# design.net
KiCad netlist of a schematic drawn in EAGLE
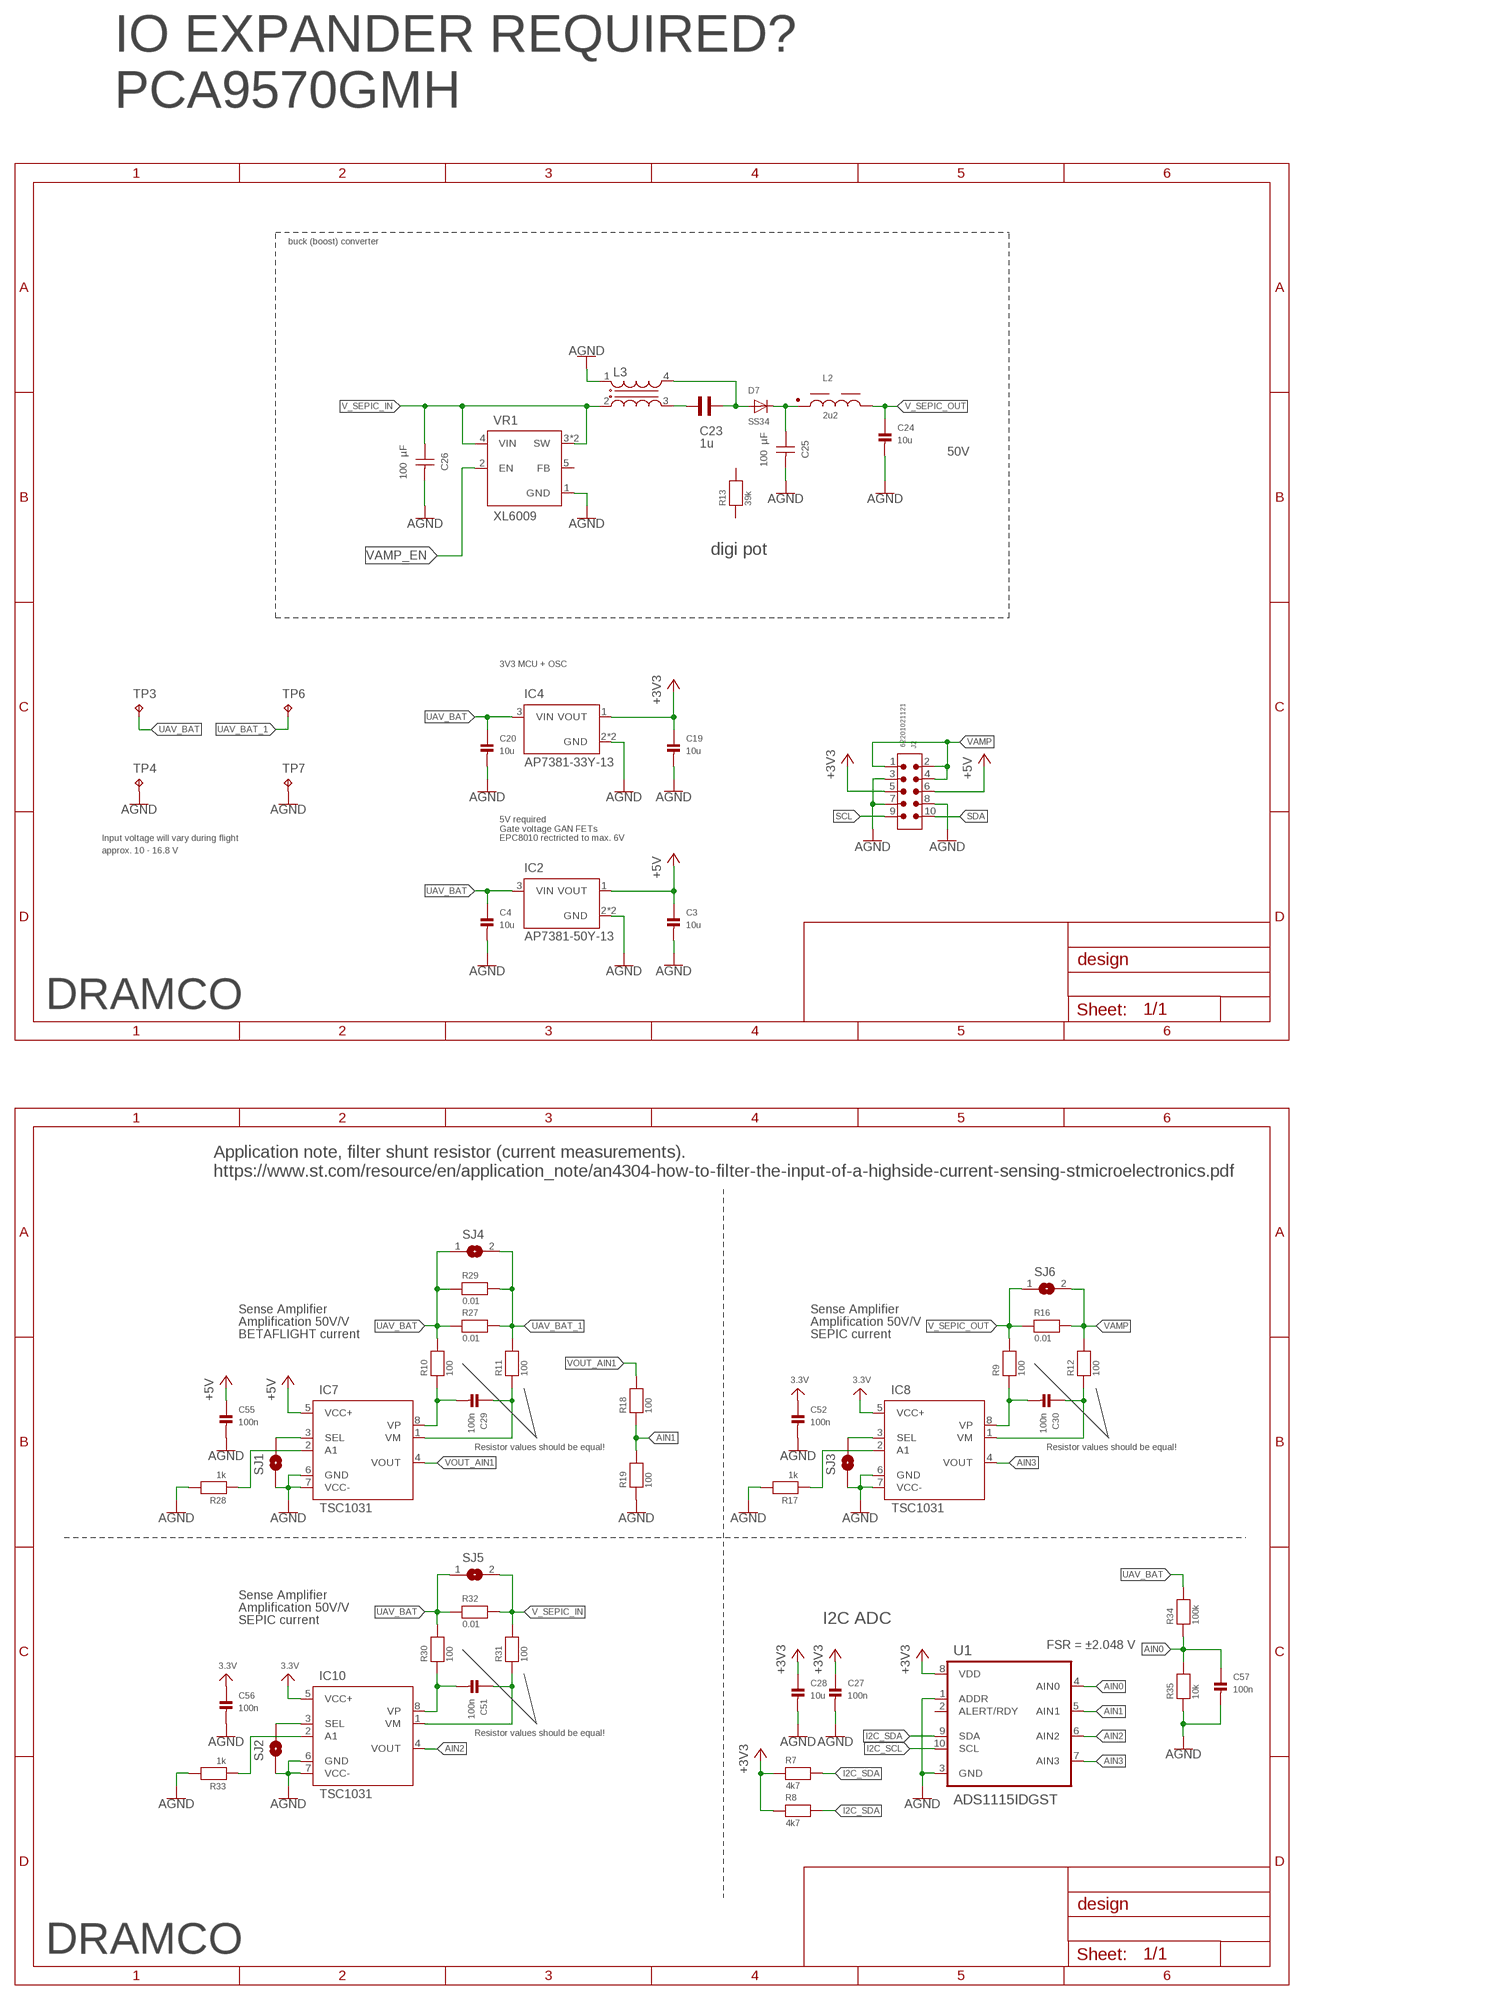
[diagram p0: schematic, sheet 1]

(export (version "E")
  (design (tool "Eeschema 10.0.6"))
  (components
    (comp (ref "C3")
      (value "10u")
      (footprint "eagle-import:0603")
      (libsource (lib "eagle-import") (part "CAP_CERAMIC0603"))
    )
    (comp (ref "C4")
      (value "10u")
      (footprint "eagle-import:0603")
      (libsource (lib "eagle-import") (part "CAP_CERAMIC0603"))
    )
    (comp (ref "C19")
      (value "10u")
      (footprint "eagle-import:0603")
      (libsource (lib "eagle-import") (part "CAP_CERAMIC0603"))
    )
    (comp (ref "C20")
      (value "10u")
      (footprint "eagle-import:0603")
      (libsource (lib "eagle-import") (part "CAP_CERAMIC0603"))
    )
    (comp (ref "C23")
      (value "1u")
      (footprint "eagle-import:WCAP-CSGP_0805_WAVE")
      (libsource (lib "eagle-import") (part "WCAP-CSGP_0805_WAVE_885012207103"))
    )
    (comp (ref "C24")
      (value "10u")
      (footprint "eagle-import:0805")
      (libsource (lib "eagle-import") (part "CAP_CERAMIC0805"))
    )
    (comp (ref "C25")
      (value "100 µF")
      (footprint "eagle-import:WCAP-ASNP_8X10.5(DXL)")
      (libsource (lib "eagle-import") (part "WCAP-ASNP_8X10.5_865250453009"))
    )
    (comp (ref "C26")
      (value "100 µF")
      (footprint "eagle-import:WCAP-ASNP_8X10.5(DXL)")
      (libsource (lib "eagle-import") (part "WCAP-ASNP_8X10.5_865250453009"))
    )
    (comp (ref "C27")
      (value "100n")
      (footprint "eagle-import:0603")
      (libsource (lib "eagle-import") (part "CAP_CERAMIC0603"))
    )
    (comp (ref "C28")
      (value "10u")
      (footprint "eagle-import:0603")
      (libsource (lib "eagle-import") (part "CAP_CERAMIC0603"))
    )
    (comp (ref "C29")
      (value "100n")
      (footprint "eagle-import:0402")
      (libsource (lib "eagle-import") (part "CAP_CERAMIC0402"))
    )
    (comp (ref "C30")
      (value "100n")
      (footprint "eagle-import:0402")
      (libsource (lib "eagle-import") (part "CAP_CERAMIC0402"))
    )
    (comp (ref "C51")
      (value "100n")
      (footprint "eagle-import:0402")
      (libsource (lib "eagle-import") (part "CAP_CERAMIC0402"))
    )
    (comp (ref "C52")
      (value "100n")
      (footprint "eagle-import:0402")
      (libsource (lib "eagle-import") (part "CAP_CERAMIC0402"))
    )
    (comp (ref "C55")
      (value "100n")
      (footprint "eagle-import:0402")
      (libsource (lib "eagle-import") (part "CAP_CERAMIC0402"))
    )
    (comp (ref "C56")
      (value "100n")
      (footprint "eagle-import:0402")
      (libsource (lib "eagle-import") (part "CAP_CERAMIC0402"))
    )
    (comp (ref "C57")
      (value "100n")
      (footprint "eagle-import:0603")
      (libsource (lib "eagle-import") (part "CAP_CERAMIC0603"))
    )
    (comp (ref "D7")
      (value "SS34")
      (footprint "eagle-import:SOD-123")
      (libsource (lib "eagle-import") (part "DIODESOD-123"))
    )
    (comp (ref "IC2")
      (value "AP7381-50Y-13")
      (footprint "eagle-import:FOOT_XC6201P332PR-G")
      (fields (field (name "MF") "Microchip") (field (name "MP") "MCP1700T-3602E/MB"))
      (libsource (lib "eagle-import") (part "AP7381-50Y-13"))
    )
    (comp (ref "IC4")
      (value "AP7381-33Y-13")
      (footprint "eagle-import:FOOT_XC6201P332PR-G")
      (fields (field (name "MF") "Microchip") (field (name "MP") "MCP1700T-3602E/MB"))
      (libsource (lib "eagle-import") (part "AP7381-50Y-13"))
    )
    (comp (ref "IC7")
      (value "TSC1031")
      (footprint "eagle-import:SOP65P640X120-8N")
      (libsource (lib "eagle-import") (part "TSC1031IPT"))
    )
    (comp (ref "IC8")
      (value "TSC1031")
      (footprint "eagle-import:SOP65P640X120-8N")
      (libsource (lib "eagle-import") (part "TSC1031IPT"))
    )
    (comp (ref "IC10")
      (value "TSC1031")
      (footprint "eagle-import:SOP65P640X120-8N")
      (libsource (lib "eagle-import") (part "TSC1031IPT"))
    )
    (comp (ref "J2")
      (value "62201021121")
      (footprint "eagle-import:62201021121")
      (libsource (lib "eagle-import") (part "6220XX21121_62201021121"))
    )
    (comp (ref "L2")
      (value "2u2")
      (footprint "eagle-import:WE-LQS_3015")
      (libsource (lib "eagle-import") (part "WE-LQS_3015_74404032022"))
    )
    (comp (ref "L3")
      (value "WE-DD_1280_744873150")
      (footprint "eagle-import:WE-DD_1260_1280")
      (libsource (lib "eagle-import") (part "WE-DD_1280_744873150"))
    )
    (comp (ref "R7")
      (value "4k7")
      (footprint "eagle-import:0603")
      (libsource (lib "eagle-import") (part "RESISTOR0603"))
    )
    (comp (ref "R8")
      (value "4k7")
      (footprint "eagle-import:0603")
      (libsource (lib "eagle-import") (part "RESISTOR0603"))
    )
    (comp (ref "R9")
      (value "100")
      (footprint "eagle-import:0603")
      (libsource (lib "eagle-import") (part "RESISTOR0603"))
    )
    (comp (ref "R10")
      (value "100")
      (footprint "eagle-import:0603")
      (libsource (lib "eagle-import") (part "RESISTOR0603"))
    )
    (comp (ref "R11")
      (value "100")
      (footprint "eagle-import:0603")
      (libsource (lib "eagle-import") (part "RESISTOR0603"))
    )
    (comp (ref "R12")
      (value "100")
      (footprint "eagle-import:0603")
      (libsource (lib "eagle-import") (part "RESISTOR0603"))
    )
    (comp (ref "R13")
      (value "39k")
      (footprint "eagle-import:0603")
      (libsource (lib "eagle-import") (part "RESISTOR0603"))
    )
    (comp (ref "R16")
      (value "0.01")
      (footprint "eagle-import:0805")
      (libsource (lib "eagle-import") (part "RESISTOR0805"))
    )
    (comp (ref "R17")
      (value "1k")
      (footprint "eagle-import:0603")
      (libsource (lib "eagle-import") (part "RESISTOR0603"))
    )
    (comp (ref "R18")
      (value "100")
      (footprint "eagle-import:0603")
      (libsource (lib "eagle-import") (part "RESISTOR0603"))
    )
    (comp (ref "R19")
      (value "100")
      (footprint "eagle-import:0603")
      (libsource (lib "eagle-import") (part "RESISTOR0603"))
    )
    (comp (ref "R27")
      (value "0.01")
      (footprint "eagle-import:0805")
      (libsource (lib "eagle-import") (part "RESISTOR0805"))
    )
    (comp (ref "R28")
      (value "1k")
      (footprint "eagle-import:0603")
      (libsource (lib "eagle-import") (part "RESISTOR0603"))
    )
    (comp (ref "R29")
      (value "0.01")
      (footprint "eagle-import:0805")
      (libsource (lib "eagle-import") (part "RESISTOR0805"))
    )
    (comp (ref "R30")
      (value "100")
      (footprint "eagle-import:0603")
      (libsource (lib "eagle-import") (part "RESISTOR0603"))
    )
    (comp (ref "R31")
      (value "100")
      (footprint "eagle-import:0603")
      (libsource (lib "eagle-import") (part "RESISTOR0603"))
    )
    (comp (ref "R32")
      (value "0.01")
      (footprint "eagle-import:0805")
      (libsource (lib "eagle-import") (part "RESISTOR0805"))
    )
    (comp (ref "R33")
      (value "1k")
      (footprint "eagle-import:0603")
      (libsource (lib "eagle-import") (part "RESISTOR0603"))
    )
    (comp (ref "R34")
      (value "100k")
      (footprint "eagle-import:0603")
      (libsource (lib "eagle-import") (part "RESISTOR0603"))
    )
    (comp (ref "R35")
      (value "10k")
      (footprint "eagle-import:0603")
      (libsource (lib "eagle-import") (part "RESISTOR0603"))
    )
    (comp (ref "SJ1")
      (value "SOLDERJUMPERTRACE")
      (footprint "eagle-import:SJ_2S-TRACE")
      (libsource (lib "eagle-import") (part "SOLDERJUMPERTRACE"))
    )
    (comp (ref "SJ2")
      (value "SOLDERJUMPERTRACE")
      (footprint "eagle-import:SJ_2S-TRACE")
      (libsource (lib "eagle-import") (part "SOLDERJUMPERTRACE"))
    )
    (comp (ref "SJ3")
      (value "SOLDERJUMPERTRACE")
      (footprint "eagle-import:SJ_2S-TRACE")
      (libsource (lib "eagle-import") (part "SOLDERJUMPERTRACE"))
    )
    (comp (ref "SJ4")
      (value "SOLDERJUMPERREFLOW")
      (footprint "eagle-import:SOLDERJUMPER_REFLOW")
      (libsource (lib "eagle-import") (part "SOLDERJUMPERREFLOW"))
    )
    (comp (ref "SJ5")
      (value "SOLDERJUMPERREFLOW")
      (footprint "eagle-import:SOLDERJUMPER_REFLOW")
      (libsource (lib "eagle-import") (part "SOLDERJUMPERREFLOW"))
    )
    (comp (ref "SJ6")
      (value "SOLDERJUMPERREFLOW")
      (footprint "eagle-import:SOLDERJUMPER_REFLOW")
      (libsource (lib "eagle-import") (part "SOLDERJUMPERREFLOW"))
    )
    (comp (ref "TP3")
      (value "TPTP20SQ")
      (footprint "eagle-import:TP20SQ")
      (libsource (lib "eagle-import") (part "TPTP20SQ"))
    )
    (comp (ref "TP4")
      (value "TPTP20SQ")
      (footprint "eagle-import:TP20SQ")
      (libsource (lib "eagle-import") (part "TPTP20SQ"))
    )
    (comp (ref "TP6")
      (value "TPTP20SQ")
      (footprint "eagle-import:TP20SQ")
      (libsource (lib "eagle-import") (part "TPTP20SQ"))
    )
    (comp (ref "TP7")
      (value "TPTP20SQ")
      (footprint "eagle-import:TP20SQ")
      (libsource (lib "eagle-import") (part "TPTP20SQ"))
    )
    (comp (ref "U1")
      (value "ADS1115IDGST")
      (footprint "eagle-import:SOP50P490X110-10N")
      (fields (field (name "MF") "Texas Instruments"))
      (libsource (lib "eagle-import") (part "ADS1115IDGST"))
    )
    (comp (ref "VR1")
      (value "XL6009")
      (footprint "eagle-import:DPAK170P1435X465-6N")
      (fields (field (name "MF") "XLSEMI"))
      (libsource (lib "eagle-import") (part "XL6009"))
    )
  )
  (nets
    (net (code "1") (name "+3V3") (class "Default")
      (node (ref "C19") (pin "1") (pinfunction "P$1_1") (pintype "passive"))
      (node (ref "C27") (pin "1") (pinfunction "P$1_1") (pintype "passive"))
      (node (ref "C28") (pin "1") (pinfunction "P$1_1") (pintype "passive"))
      (node (ref "IC4") (pin "1") (pinfunction "VOUT_1") (pintype "output"))
      (node (ref "J2") (pin "5") (pinfunction "5_5") (pintype "passive"))
      (node (ref "R7") (pin "1") (pinfunction "1_1") (pintype "passive"))
      (node (ref "R8") (pin "1") (pinfunction "1_1") (pintype "passive"))
      (node (ref "U1") (pin "8") (pinfunction "VDD_8") (pintype "power_in"))
    )
    (net (code "2") (name "+5V") (class "Default")
      (node (ref "C3") (pin "1") (pinfunction "P$1_1") (pintype "passive"))
      (node (ref "C55") (pin "1") (pinfunction "P$1_1") (pintype "passive"))
      (node (ref "IC2") (pin "1") (pinfunction "VOUT_1") (pintype "output"))
      (node (ref "IC7") (pin "5") (pinfunction "VCC+_5") (pintype "bidirectional"))
      (node (ref "J2") (pin "6") (pinfunction "6_6") (pintype "passive"))
    )
    (net (code "3") (name "3.3V") (class "Default")
      (node (ref "C52") (pin "1") (pinfunction "P$1_1") (pintype "passive"))
      (node (ref "C56") (pin "1") (pinfunction "P$1_1") (pintype "passive"))
      (node (ref "IC10") (pin "5") (pinfunction "VCC+_5") (pintype "bidirectional"))
      (node (ref "IC8") (pin "5") (pinfunction "VCC+_5") (pintype "bidirectional"))
    )
    (net (code "4") (name "AGND") (class "Default")
      (node (ref "C19") (pin "2") (pinfunction "P$2_2") (pintype "passive"))
      (node (ref "C20") (pin "2") (pinfunction "P$2_2") (pintype "passive"))
      (node (ref "C24") (pin "2") (pinfunction "P$2_2") (pintype "passive"))
      (node (ref "C25") (pin "2") (pinfunction "2_2") (pintype "passive"))
      (node (ref "C26") (pin "2") (pinfunction "2_2") (pintype "passive"))
      (node (ref "C27") (pin "2") (pinfunction "P$2_2") (pintype "passive"))
      (node (ref "C28") (pin "2") (pinfunction "P$2_2") (pintype "passive"))
      (node (ref "C3") (pin "2") (pinfunction "P$2_2") (pintype "passive"))
      (node (ref "C4") (pin "2") (pinfunction "P$2_2") (pintype "passive"))
      (node (ref "C52") (pin "2") (pinfunction "P$2_2") (pintype "passive"))
      (node (ref "C55") (pin "2") (pinfunction "P$2_2") (pintype "passive"))
      (node (ref "C56") (pin "2") (pinfunction "P$2_2") (pintype "passive"))
      (node (ref "C57") (pin "2") (pinfunction "P$2_2") (pintype "passive"))
      (node (ref "IC10") (pin "6") (pinfunction "GND_6") (pintype "bidirectional"))
      (node (ref "IC10") (pin "7") (pinfunction "VCC-_7") (pintype "bidirectional"))
      (node (ref "IC2") (pin "2") (pinfunction "GND_2") (pintype "power_in"))
      (node (ref "IC2") (pin "2.1") (pinfunction "GND_2.1") (pintype "power_in"))
      (node (ref "IC4") (pin "2") (pinfunction "GND_2") (pintype "power_in"))
      (node (ref "IC4") (pin "2.1") (pinfunction "GND_2.1") (pintype "power_in"))
      (node (ref "IC7") (pin "6") (pinfunction "GND_6") (pintype "bidirectional"))
      (node (ref "IC7") (pin "7") (pinfunction "VCC-_7") (pintype "bidirectional"))
      (node (ref "IC8") (pin "6") (pinfunction "GND_6") (pintype "bidirectional"))
      (node (ref "IC8") (pin "7") (pinfunction "VCC-_7") (pintype "bidirectional"))
      (node (ref "J2") (pin "3") (pinfunction "3_3") (pintype "passive"))
      (node (ref "J2") (pin "7") (pinfunction "7_7") (pintype "passive"))
      (node (ref "J2") (pin "8") (pinfunction "8_8") (pintype "passive"))
      (node (ref "L3") (pin "1") (pinfunction "1_1") (pintype "passive"))
      (node (ref "R17") (pin "2") (pinfunction "2_2") (pintype "passive"))
      (node (ref "R19") (pin "1") (pinfunction "1_1") (pintype "passive"))
      (node (ref "R28") (pin "2") (pinfunction "2_2") (pintype "passive"))
      (node (ref "R33") (pin "2") (pinfunction "2_2") (pintype "passive"))
      (node (ref "R35") (pin "1") (pinfunction "1_1") (pintype "passive"))
      (node (ref "SJ1") (pin "1") (pinfunction "1_1") (pintype "passive"))
      (node (ref "SJ2") (pin "1") (pinfunction "1_1") (pintype "passive"))
      (node (ref "SJ3") (pin "1") (pinfunction "1_1") (pintype "passive"))
      (node (ref "TP4") (pin "TP") (pinfunction "TP_TP") (pintype "input"))
      (node (ref "TP7") (pin "TP") (pinfunction "TP_TP") (pintype "input"))
      (node (ref "U1") (pin "1") (pinfunction "ADDR_1") (pintype "input"))
      (node (ref "U1") (pin "3") (pinfunction "GND_3") (pintype "passive"))
      (node (ref "VR1") (pin "1") (pinfunction "GND_1") (pintype "power_in"))
    )
    (net (code "5") (name "AIN0") (class "Default")
      (node (ref "C57") (pin "1") (pinfunction "P$1_1") (pintype "passive"))
      (node (ref "R34") (pin "1") (pinfunction "1_1") (pintype "passive"))
      (node (ref "R35") (pin "2") (pinfunction "2_2") (pintype "passive"))
      (node (ref "U1") (pin "4") (pinfunction "AIN0_4") (pintype "input"))
    )
    (net (code "6") (name "AIN1") (class "Default")
      (node (ref "R18") (pin "1") (pinfunction "1_1") (pintype "passive"))
      (node (ref "R19") (pin "2") (pinfunction "2_2") (pintype "passive"))
      (node (ref "U1") (pin "5") (pinfunction "AIN1_5") (pintype "input"))
    )
    (net (code "7") (name "AIN2") (class "Default")
      (node (ref "IC10") (pin "4") (pinfunction "VOUT_4") (pintype "bidirectional"))
      (node (ref "U1") (pin "6") (pinfunction "AIN2_6") (pintype "input"))
    )
    (net (code "8") (name "AIN3") (class "Default")
      (node (ref "IC8") (pin "4") (pinfunction "VOUT_4") (pintype "bidirectional"))
      (node (ref "U1") (pin "7") (pinfunction "AIN3_7") (pintype "input"))
    )
    (net (code "9") (name "I2C_SCL") (class "Default")
      (node (ref "U1") (pin "10") (pinfunction "SCL_10") (pintype "input"))
    )
    (net (code "10") (name "I2C_SDA") (class "Default")
      (node (ref "R7") (pin "2") (pinfunction "2_2") (pintype "passive"))
      (node (ref "R8") (pin "2") (pinfunction "2_2") (pintype "passive"))
      (node (ref "U1") (pin "9") (pinfunction "SDA_9") (pintype "bidirectional"))
    )
    (net (code "11") (name "Net-(C23-Pad2)") (class "Default")
      (node (ref "C23") (pin "2") (pinfunction "2_2") (pintype "passive"))
      (node (ref "L3") (pin "3") (pinfunction "3_3") (pintype "passive"))
    )
    (net (code "12") (name "Net-(C25-Pad1)") (class "Default")
      (node (ref "C25") (pin "1") (pinfunction "1_1") (pintype "passive"))
      (node (ref "D7") (pin "C") (pinfunction "C_C") (pintype "passive"))
      (node (ref "L2") (pin "1") (pinfunction "1_1") (pintype "passive"))
    )
    (net (code "13") (name "Net-(C29-P$1)") (class "Default")
      (node (ref "C29") (pin "1") (pinfunction "P$1_1") (pintype "passive"))
      (node (ref "IC7") (pin "1") (pinfunction "VM_1") (pintype "bidirectional"))
      (node (ref "R11") (pin "1") (pinfunction "1_1") (pintype "passive"))
    )
    (net (code "14") (name "Net-(C29-P$2)") (class "Default")
      (node (ref "C29") (pin "2") (pinfunction "P$2_2") (pintype "passive"))
      (node (ref "IC7") (pin "8") (pinfunction "VP_8") (pintype "bidirectional"))
      (node (ref "R10") (pin "1") (pinfunction "1_1") (pintype "passive"))
    )
    (net (code "15") (name "Net-(C30-P$1)") (class "Default")
      (node (ref "C30") (pin "1") (pinfunction "P$1_1") (pintype "passive"))
      (node (ref "IC8") (pin "1") (pinfunction "VM_1") (pintype "bidirectional"))
      (node (ref "R12") (pin "1") (pinfunction "1_1") (pintype "passive"))
    )
    (net (code "16") (name "Net-(C30-P$2)") (class "Default")
      (node (ref "C30") (pin "2") (pinfunction "P$2_2") (pintype "passive"))
      (node (ref "IC8") (pin "8") (pinfunction "VP_8") (pintype "bidirectional"))
      (node (ref "R9") (pin "1") (pinfunction "1_1") (pintype "passive"))
    )
    (net (code "17") (name "Net-(C51-P$1)") (class "Default")
      (node (ref "C51") (pin "1") (pinfunction "P$1_1") (pintype "passive"))
      (node (ref "IC10") (pin "1") (pinfunction "VM_1") (pintype "bidirectional"))
      (node (ref "R31") (pin "1") (pinfunction "1_1") (pintype "passive"))
    )
    (net (code "18") (name "Net-(C51-P$2)") (class "Default")
      (node (ref "C51") (pin "2") (pinfunction "P$2_2") (pintype "passive"))
      (node (ref "IC10") (pin "8") (pinfunction "VP_8") (pintype "bidirectional"))
      (node (ref "R30") (pin "1") (pinfunction "1_1") (pintype "passive"))
    )
    (net (code "19") (name "Net-(IC7-A1)") (class "Default")
      (node (ref "IC7") (pin "2") (pinfunction "A1_2") (pintype "bidirectional"))
      (node (ref "R28") (pin "1") (pinfunction "1_1") (pintype "passive"))
    )
    (net (code "20") (name "Net-(IC7-SEL)") (class "Default")
      (node (ref "IC7") (pin "3") (pinfunction "SEL_3") (pintype "bidirectional"))
      (node (ref "SJ1") (pin "2") (pinfunction "2_2") (pintype "passive"))
    )
    (net (code "21") (name "Net-(IC8-A1)") (class "Default")
      (node (ref "IC8") (pin "2") (pinfunction "A1_2") (pintype "bidirectional"))
      (node (ref "R17") (pin "1") (pinfunction "1_1") (pintype "passive"))
    )
    (net (code "22") (name "Net-(IC8-SEL)") (class "Default")
      (node (ref "IC8") (pin "3") (pinfunction "SEL_3") (pintype "bidirectional"))
      (node (ref "SJ3") (pin "2") (pinfunction "2_2") (pintype "passive"))
    )
    (net (code "23") (name "Net-(IC10-A1)") (class "Default")
      (node (ref "IC10") (pin "2") (pinfunction "A1_2") (pintype "bidirectional"))
      (node (ref "R33") (pin "1") (pinfunction "1_1") (pintype "passive"))
    )
    (net (code "24") (name "Net-(IC10-SEL)") (class "Default")
      (node (ref "IC10") (pin "3") (pinfunction "SEL_3") (pintype "bidirectional"))
      (node (ref "SJ2") (pin "2") (pinfunction "2_2") (pintype "passive"))
    )
    (net (code "25") (name "Net-(L3-2)") (class "Default")
      (node (ref "C23") (pin "1") (pinfunction "1_1") (pintype "passive"))
      (node (ref "D7") (pin "A") (pinfunction "A_A") (pintype "passive"))
      (node (ref "L3") (pin "4") (pinfunction "2_4") (pintype "passive"))
    )
    (net (code "26") (name "SCL") (class "Default")
      (node (ref "J2") (pin "9") (pinfunction "9_9") (pintype "passive"))
    )
    (net (code "27") (name "SDA") (class "Default")
      (node (ref "J2") (pin "10") (pinfunction "10_10") (pintype "passive"))
    )
    (net (code "28") (name "UAV_BAT") (class "Default")
      (node (ref "C20") (pin "1") (pinfunction "P$1_1") (pintype "passive"))
      (node (ref "C4") (pin "1") (pinfunction "P$1_1") (pintype "passive"))
      (node (ref "IC2") (pin "3") (pinfunction "VIN_3") (pintype "input"))
      (node (ref "IC4") (pin "3") (pinfunction "VIN_3") (pintype "input"))
      (node (ref "R10") (pin "2") (pinfunction "2_2") (pintype "passive"))
      (node (ref "R27") (pin "1") (pinfunction "1_1") (pintype "passive"))
      (node (ref "R29") (pin "1") (pinfunction "1_1") (pintype "passive"))
      (node (ref "R30") (pin "2") (pinfunction "2_2") (pintype "passive"))
      (node (ref "R32") (pin "1") (pinfunction "1_1") (pintype "passive"))
      (node (ref "R34") (pin "2") (pinfunction "2_2") (pintype "passive"))
      (node (ref "SJ4") (pin "1") (pinfunction "1_1") (pintype "passive"))
      (node (ref "SJ5") (pin "1") (pinfunction "1_1") (pintype "passive"))
      (node (ref "TP3") (pin "TP") (pinfunction "TP_TP") (pintype "input"))
    )
    (net (code "29") (name "UAV_BAT_1") (class "Default")
      (node (ref "R11") (pin "2") (pinfunction "2_2") (pintype "passive"))
      (node (ref "R27") (pin "2") (pinfunction "2_2") (pintype "passive"))
      (node (ref "R29") (pin "2") (pinfunction "2_2") (pintype "passive"))
      (node (ref "SJ4") (pin "2") (pinfunction "2_2") (pintype "passive"))
      (node (ref "TP6") (pin "TP") (pinfunction "TP_TP") (pintype "input"))
    )
    (net (code "30") (name "VAMP") (class "Default")
      (node (ref "J2") (pin "1") (pinfunction "1_1") (pintype "passive"))
      (node (ref "J2") (pin "2") (pinfunction "2_2") (pintype "passive"))
      (node (ref "J2") (pin "4") (pinfunction "4_4") (pintype "passive"))
      (node (ref "R12") (pin "2") (pinfunction "2_2") (pintype "passive"))
      (node (ref "R16") (pin "2") (pinfunction "2_2") (pintype "passive"))
      (node (ref "SJ6") (pin "2") (pinfunction "2_2") (pintype "passive"))
    )
    (net (code "31") (name "VAMP_EN") (class "Default")
      (node (ref "VR1") (pin "2") (pinfunction "EN_2") (pintype "input"))
    )
    (net (code "32") (name "VOUT_AIN1") (class "Default")
      (node (ref "IC7") (pin "4") (pinfunction "VOUT_4") (pintype "bidirectional"))
      (node (ref "R18") (pin "2") (pinfunction "2_2") (pintype "passive"))
    )
    (net (code "33") (name "V_SEPIC_IN") (class "Default")
      (node (ref "C26") (pin "1") (pinfunction "1_1") (pintype "passive"))
      (node (ref "L3") (pin "2") (pinfunction "4_2") (pintype "passive"))
      (node (ref "R31") (pin "2") (pinfunction "2_2") (pintype "passive"))
      (node (ref "R32") (pin "2") (pinfunction "2_2") (pintype "passive"))
      (node (ref "SJ5") (pin "2") (pinfunction "2_2") (pintype "passive"))
      (node (ref "VR1") (pin "3") (pinfunction "SW_3") (pintype "output"))
      (node (ref "VR1") (pin "4") (pinfunction "VIN_4") (pintype "input"))
      (node (ref "VR1") (pin "6") (pinfunction "SW_6") (pintype "output"))
    )
    (net (code "34") (name "V_SEPIC_OUT") (class "Default")
      (node (ref "C24") (pin "1") (pinfunction "P$1_1") (pintype "passive"))
      (node (ref "L2") (pin "2") (pinfunction "2_2") (pintype "passive"))
      (node (ref "R16") (pin "1") (pinfunction "1_1") (pintype "passive"))
      (node (ref "R9") (pin "2") (pinfunction "2_2") (pintype "passive"))
      (node (ref "SJ6") (pin "1") (pinfunction "1_1") (pintype "passive"))
    )
    (net (code "35") (name "unconnected-(R13-Pad1)") (class "Default")
      (node (ref "R13") (pin "1") (pinfunction "1_1") (pintype "passive"))
    )
    (net (code "36") (name "unconnected-(R13-Pad2)") (class "Default")
      (node (ref "R13") (pin "2") (pinfunction "2_2") (pintype "passive"))
    )
    (net (code "37") (name "unconnected-(U1-ALERT{slash}RDY-Pad2)") (class "Default")
      (node (ref "U1") (pin "2") (pinfunction "ALERT/RDY_2") (pintype "input"))
    )
    (net (code "38") (name "unconnected-(VR1-FB-Pad5)") (class "Default")
      (node (ref "VR1") (pin "5") (pinfunction "FB_5") (pintype "input"))
    )
  )
)
